# LPS25HBTR.net
KiCad netlist of a schematic drawn in EAGLE
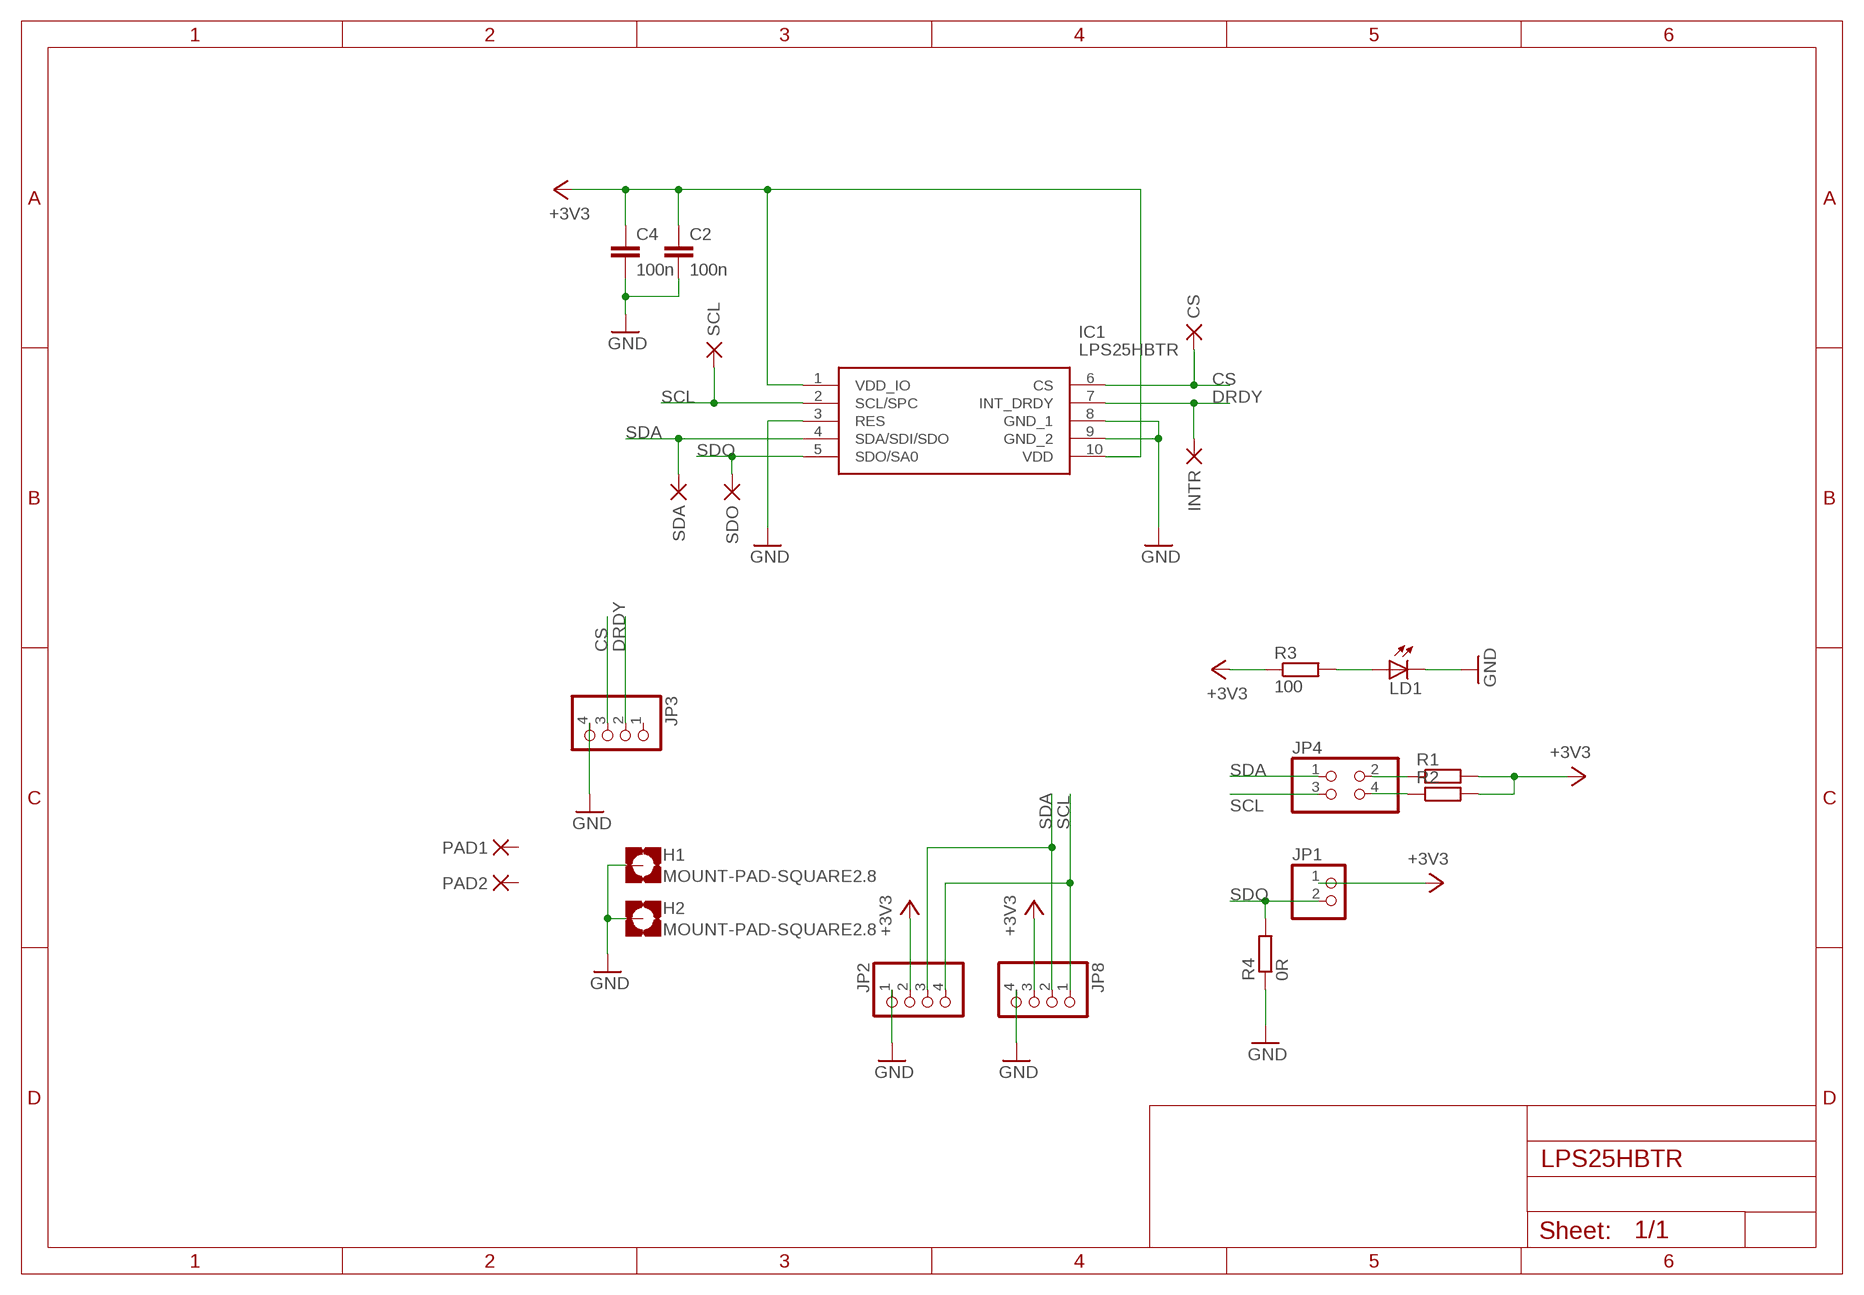
[diagram p0: schematic, sheet 1]

(export (version "E")
  (design (tool "Eeschema 10.0.6"))
  (components
    (comp (ref "C2")
      (value "100n")
      (footprint "eagle-import:C0805")
      (libsource (lib "eagle-import") (part "C-EUC0805"))
    )
    (comp (ref "C4")
      (value "100n")
      (footprint "eagle-import:C0805")
      (libsource (lib "eagle-import") (part "C-EUC0805"))
    )
    (comp (ref "CS")
      (value "PAD-SMD10R")
      (footprint "eagle-import:SMD10R")
      (libsource (lib "eagle-import") (part "PAD-SMD10R"))
    )
    (comp (ref "H1")
      (value "MOUNT-PAD-SQUARE2.8")
      (footprint "eagle-import:2,8-PAD-SQUARE")
      (libsource (lib "eagle-import") (part "MOUNT-PAD-SQUARE2.8"))
    )
    (comp (ref "H2")
      (value "MOUNT-PAD-SQUARE2.8")
      (footprint "eagle-import:2,8-PAD-SQUARE")
      (libsource (lib "eagle-import") (part "MOUNT-PAD-SQUARE2.8"))
    )
    (comp (ref "IC1")
      (value "LPS25HBTR")
      (footprint "eagle-import:PQFN60P250X250X80-10N")
      (fields (field (name "MOUSER_PART_NUMBER") "511-LPS25HBTR") (field (name "RS_PART_NUMBER") "1106550P"))
      (libsource (lib "eagle-import") (part "LPS25HBTR"))
    )
    (comp (ref "INTR")
      (value "PAD-SMD10R")
      (footprint "eagle-import:SMD10R")
      (libsource (lib "eagle-import") (part "PAD-SMD10R"))
    )
    (comp (ref "JP1")
      (value "PINHD-1X2")
      (footprint "eagle-import:1X02")
      (libsource (lib "eagle-import") (part "PINHD-1X2"))
    )
    (comp (ref "JP2")
      (value "PINHD-1X4_2.54-90°")
      (footprint "eagle-import:1X04_90")
      (libsource (lib "eagle-import") (part "PINHD-1X4_2.54-90°"))
    )
    (comp (ref "JP3")
      (value "PINHD-1X4")
      (footprint "eagle-import:1X04")
      (libsource (lib "eagle-import") (part "PINHD-1X4"))
    )
    (comp (ref "JP4")
      (value "PINHD-2X2_2.54")
      (footprint "eagle-import:2X02")
      (libsource (lib "eagle-import") (part "PINHD-2X2_2.54"))
    )
    (comp (ref "JP8")
      (value "PINHD-1X4_2.54-90°")
      (footprint "eagle-import:1X04_90")
      (libsource (lib "eagle-import") (part "PINHD-1X4_2.54-90°"))
    )
    (comp (ref "LD1")
      (value "LEDCHIPLED_0805")
      (footprint "eagle-import:CHIPLED_0805")
      (libsource (lib "eagle-import") (part "LEDCHIPLED_0805"))
    )
    (comp (ref "PAD1")
      (value "PAD-SMD10R")
      (footprint "eagle-import:SMD10R")
      (libsource (lib "eagle-import") (part "PAD-SMD10R"))
    )
    (comp (ref "PAD2")
      (value "PAD-SMD10R")
      (footprint "eagle-import:SMD10R")
      (libsource (lib "eagle-import") (part "PAD-SMD10R"))
    )
    (comp (ref "R1")
      (value "R-EU_R0805")
      (footprint "eagle-import:R0805")
      (libsource (lib "eagle-import") (part "R-EU_R0805"))
    )
    (comp (ref "R2")
      (value "R-EU_R0805")
      (footprint "eagle-import:R0805")
      (libsource (lib "eagle-import") (part "R-EU_R0805"))
    )
    (comp (ref "R3")
      (value "100")
      (footprint "eagle-import:R0805")
      (libsource (lib "eagle-import") (part "R-EU_R0805"))
    )
    (comp (ref "R4")
      (value "0R")
      (footprint "eagle-import:R0805")
      (libsource (lib "eagle-import") (part "R-EU_R0805"))
    )
    (comp (ref "SCL")
      (value "PAD-SMD10R")
      (footprint "eagle-import:SMD10R")
      (libsource (lib "eagle-import") (part "PAD-SMD10R"))
    )
    (comp (ref "SDA")
      (value "PAD-SMD10R")
      (footprint "eagle-import:SMD10R")
      (libsource (lib "eagle-import") (part "PAD-SMD10R"))
    )
    (comp (ref "SDO")
      (value "PAD-SMD10R")
      (footprint "eagle-import:SMD10R")
      (libsource (lib "eagle-import") (part "PAD-SMD10R"))
    )
  )
  (nets
    (net (code "1") (name "+3V3") (class "Default")
      (node (ref "C2") (pin "1") (pinfunction "1_1") (pintype "passive"))
      (node (ref "C4") (pin "1") (pinfunction "1_1") (pintype "passive"))
      (node (ref "IC1") (pin "1") (pinfunction "VDD_IO_1") (pintype "power_in"))
      (node (ref "IC1") (pin "10") (pinfunction "VDD_10") (pintype "power_in"))
      (node (ref "JP1") (pin "1") (pinfunction "1_1") (pintype "passive"))
      (node (ref "JP2") (pin "2") (pinfunction "2_2") (pintype "passive"))
      (node (ref "JP8") (pin "3") (pinfunction "3_3") (pintype "passive"))
      (node (ref "R1") (pin "2") (pinfunction "2_2") (pintype "passive"))
      (node (ref "R2") (pin "2") (pinfunction "2_2") (pintype "passive"))
      (node (ref "R3") (pin "1") (pinfunction "1_1") (pintype "passive"))
    )
    (net (code "2") (name "/CS") (class "Default")
      (node (ref "CS") (pin "PAD") (pinfunction "P_PAD") (pintype "passive"))
      (node (ref "IC1") (pin "6") (pinfunction "CS_6") (pintype "input"))
      (node (ref "JP3") (pin "3") (pinfunction "3_3") (pintype "passive"))
    )
    (net (code "3") (name "/DRDY") (class "Default")
      (node (ref "IC1") (pin "7") (pinfunction "INT_DRDY_7") (pintype "input"))
      (node (ref "INTR") (pin "PAD") (pinfunction "P_PAD") (pintype "passive"))
      (node (ref "JP3") (pin "2") (pinfunction "2_2") (pintype "passive"))
    )
    (net (code "4") (name "/SCL") (class "Default")
      (node (ref "IC1") (pin "2") (pinfunction "SCL/SPC_2") (pintype "bidirectional"))
      (node (ref "JP2") (pin "4") (pinfunction "4_4") (pintype "passive"))
      (node (ref "JP4") (pin "3") (pinfunction "3_3") (pintype "passive"))
      (node (ref "JP8") (pin "1") (pinfunction "1_1") (pintype "passive"))
      (node (ref "SCL") (pin "PAD") (pinfunction "P_PAD") (pintype "passive"))
    )
    (net (code "5") (name "/SDA") (class "Default")
      (node (ref "IC1") (pin "4") (pinfunction "SDA/SDI/SDO_4") (pintype "bidirectional"))
      (node (ref "JP2") (pin "3") (pinfunction "3_3") (pintype "passive"))
      (node (ref "JP4") (pin "1") (pinfunction "1_1") (pintype "passive"))
      (node (ref "JP8") (pin "2") (pinfunction "2_2") (pintype "passive"))
      (node (ref "SDA") (pin "PAD") (pinfunction "P_PAD") (pintype "passive"))
    )
    (net (code "6") (name "/SDO") (class "Default")
      (node (ref "IC1") (pin "5") (pinfunction "SDO/SA0_5") (pintype "bidirectional"))
      (node (ref "JP1") (pin "2") (pinfunction "2_2") (pintype "passive"))
      (node (ref "R4") (pin "2") (pinfunction "2_2") (pintype "passive"))
      (node (ref "SDO") (pin "PAD") (pinfunction "P_PAD") (pintype "passive"))
    )
    (net (code "7") (name "GND") (class "Default")
      (node (ref "C2") (pin "2") (pinfunction "2_2") (pintype "passive"))
      (node (ref "C4") (pin "2") (pinfunction "2_2") (pintype "passive"))
      (node (ref "H1") (pin "B2,8") (pinfunction "MOUNT_B2,8") (pintype "passive"))
      (node (ref "H2") (pin "B2,8") (pinfunction "MOUNT_B2,8") (pintype "passive"))
      (node (ref "IC1") (pin "3") (pinfunction "RES_3") (pintype "bidirectional"))
      (node (ref "IC1") (pin "8") (pinfunction "GND_1_8") (pintype "power_in"))
      (node (ref "IC1") (pin "9") (pinfunction "GND_2_9") (pintype "power_in"))
      (node (ref "JP2") (pin "1") (pinfunction "1_1") (pintype "passive"))
      (node (ref "JP3") (pin "4") (pinfunction "4_4") (pintype "passive"))
      (node (ref "JP8") (pin "4") (pinfunction "4_4") (pintype "passive"))
      (node (ref "LD1") (pin "C") (pinfunction "C_C") (pintype "passive"))
      (node (ref "R4") (pin "1") (pinfunction "1_1") (pintype "passive"))
    )
    (net (code "8") (name "Net-(JP4-Pad2)") (class "Default")
      (node (ref "JP4") (pin "2") (pinfunction "2_2") (pintype "passive"))
      (node (ref "R1") (pin "1") (pinfunction "1_1") (pintype "passive"))
    )
    (net (code "9") (name "Net-(JP4-Pad4)") (class "Default")
      (node (ref "JP4") (pin "4") (pinfunction "4_4") (pintype "passive"))
      (node (ref "R2") (pin "1") (pinfunction "1_1") (pintype "passive"))
    )
    (net (code "10") (name "Net-(LD1-PadA)") (class "Default")
      (node (ref "LD1") (pin "A") (pinfunction "A_A") (pintype "passive"))
      (node (ref "R3") (pin "2") (pinfunction "2_2") (pintype "passive"))
    )
    (net (code "11") (name "unconnected-(JP3-Pad1)") (class "Default")
      (node (ref "JP3") (pin "1") (pinfunction "1_1") (pintype "passive"))
    )
    (net (code "12") (name "unconnected-(PAD1-P-PadPAD)") (class "Default")
      (node (ref "PAD1") (pin "PAD") (pinfunction "P_PAD") (pintype "passive"))
    )
    (net (code "13") (name "unconnected-(PAD2-P-PadPAD)") (class "Default")
      (node (ref "PAD2") (pin "PAD") (pinfunction "P_PAD") (pintype "passive"))
    )
  )
)
